# Task11.net
KiCad netlist of a schematic drawn in EAGLE
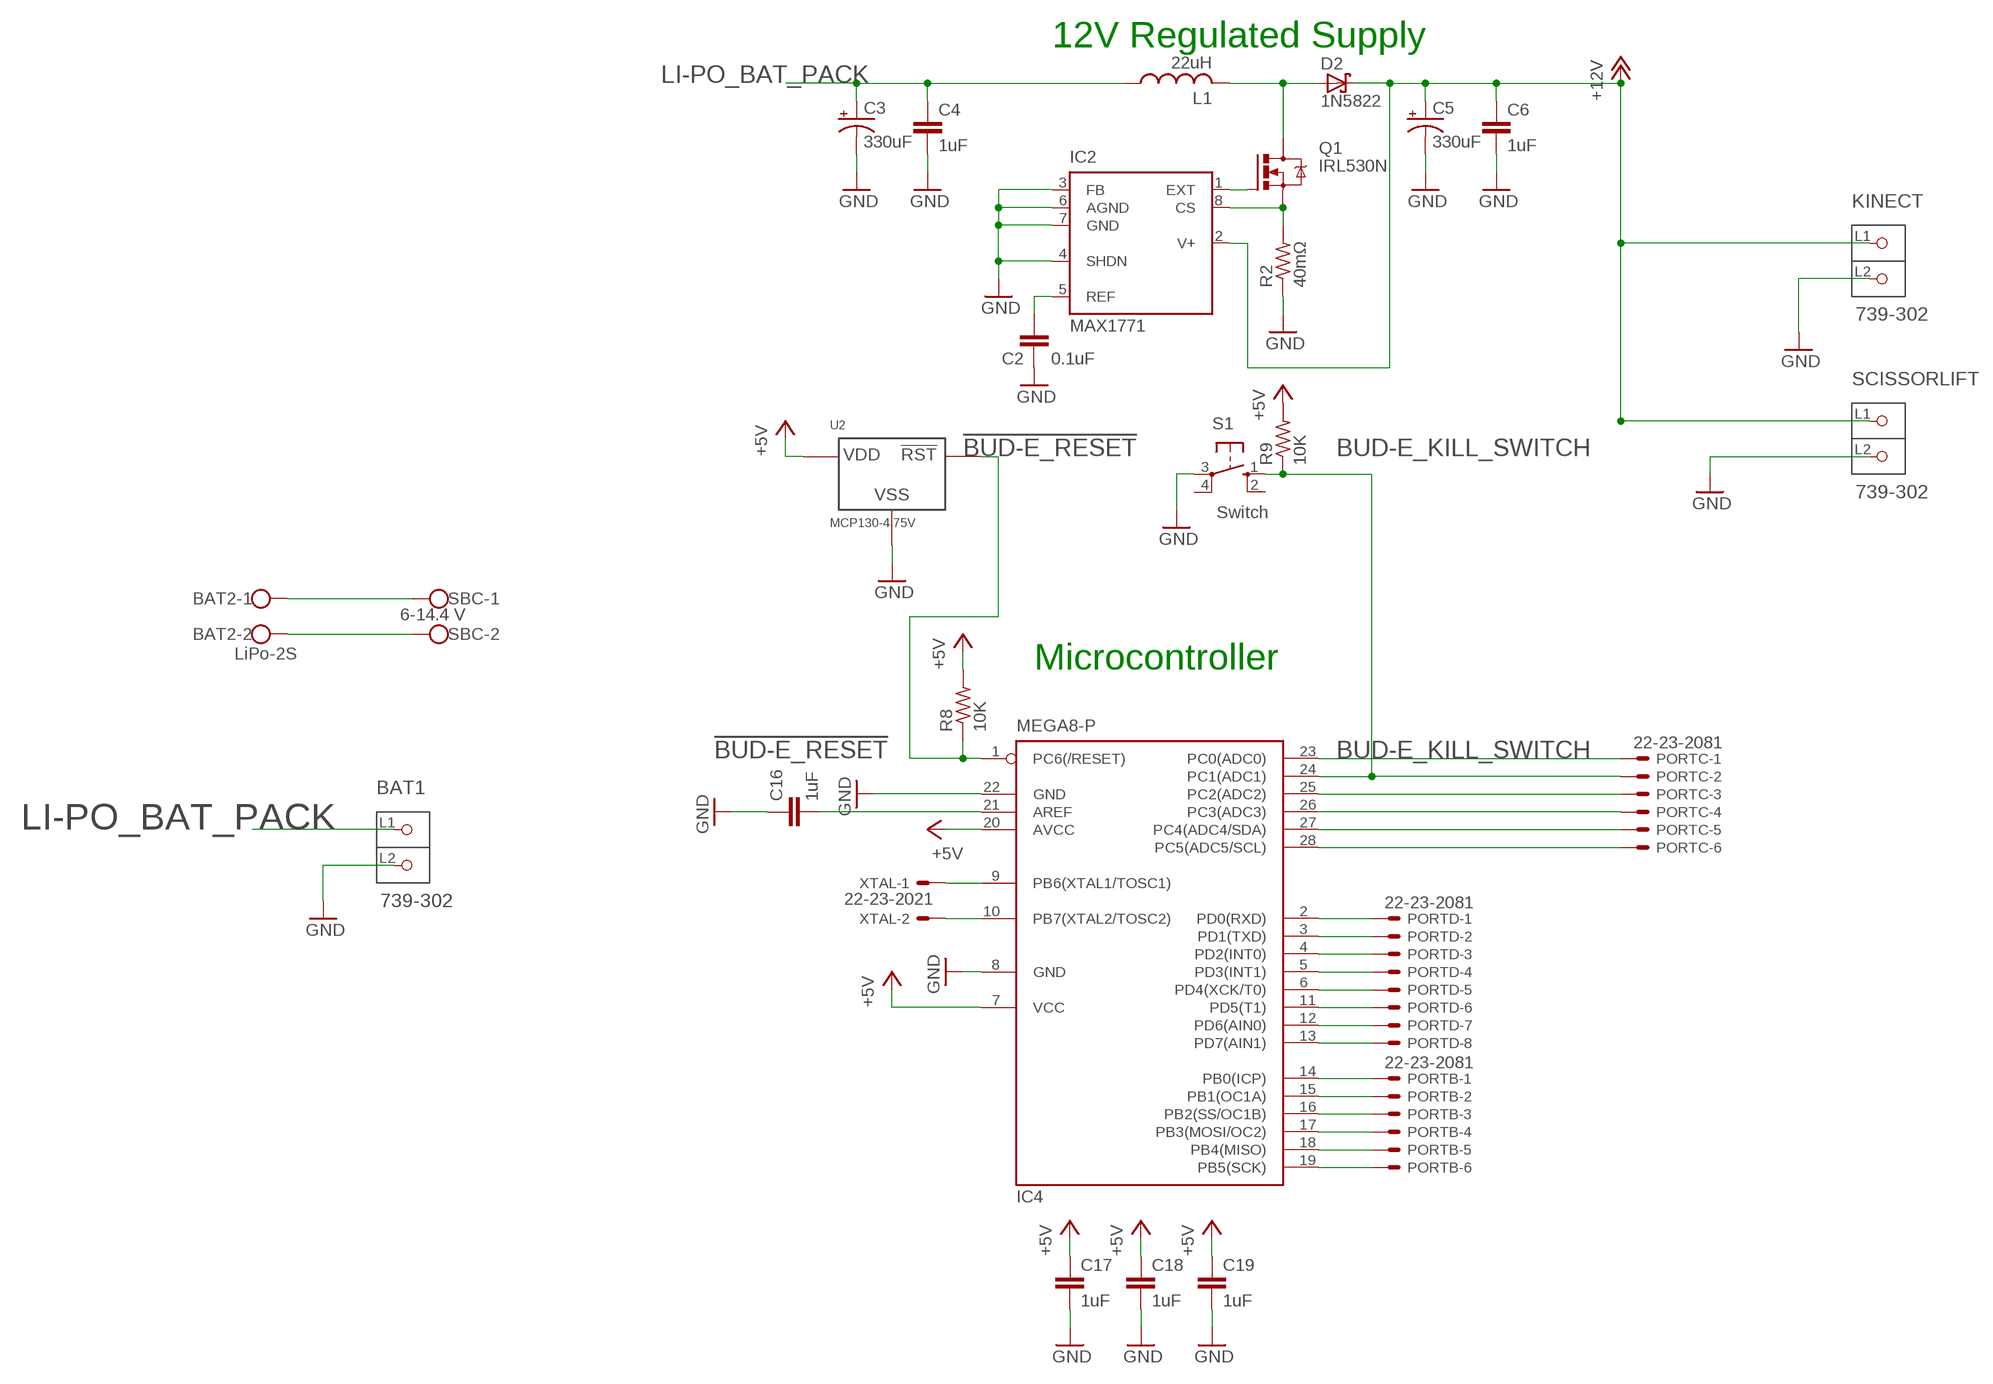
[diagram p0: schematic, sheet 1]

(export (version "E")
  (design (tool "Eeschema 10.0.6"))
  (components
    (comp (ref "BAT1")
      (value "739-302")
      (footprint "eagle-import:P-739-302")
      (libsource (lib "eagle-import") (part "739-302"))
    )
    (comp (ref "BAT2")
      (value "LiPo-2S")
      (footprint "eagle-import:W237-113")
      (libsource (lib "eagle-import") (part "W237-113"))
    )
    (comp (ref "C2")
      (value "0.1uF")
      (footprint "eagle-import:C025-025X050")
      (libsource (lib "eagle-import") (part "C-EU025-025X050"))
    )
    (comp (ref "C3")
      (value "330uF")
      (footprint "eagle-import:E2,5-6")
      (libsource (lib "eagle-import") (part "CPOL-USE2.5-6"))
    )
    (comp (ref "C4")
      (value "1uF")
      (footprint "eagle-import:C025-025X050")
      (libsource (lib "eagle-import") (part "C-EU025-025X050"))
    )
    (comp (ref "C5")
      (value "330uF")
      (footprint "eagle-import:E2,5-6")
      (libsource (lib "eagle-import") (part "CPOL-USE2.5-6"))
    )
    (comp (ref "C6")
      (value "1uF")
      (footprint "eagle-import:C025-025X050")
      (libsource (lib "eagle-import") (part "C-EU025-025X050"))
    )
    (comp (ref "C16")
      (value "1uF")
      (footprint "eagle-import:C025-025X050")
      (libsource (lib "eagle-import") (part "C-EU025-025X050"))
    )
    (comp (ref "C17")
      (value "1uF")
      (footprint "eagle-import:C025-025X050")
      (libsource (lib "eagle-import") (part "C-EU025-025X050"))
    )
    (comp (ref "C18")
      (value "1uF")
      (footprint "eagle-import:C025-025X050")
      (libsource (lib "eagle-import") (part "C-EU025-025X050"))
    )
    (comp (ref "C19")
      (value "1uF")
      (footprint "eagle-import:C025-025X050")
      (libsource (lib "eagle-import") (part "C-EU025-025X050"))
    )
    (comp (ref "D2")
      (value "1N5822")
      (footprint "eagle-import:C4111-15")
      (libsource (lib "eagle-import") (part "1N5908"))
    )
    (comp (ref "IC2")
      (value "MAX1771")
      (footprint "eagle-import:DIL08")
      (libsource (lib "eagle-import") (part "MAX1771"))
    )
    (comp (ref "IC4")
      (value "MEGA8-P")
      (footprint "eagle-import:DIL28-3")
      (libsource (lib "eagle-import") (part "MEGA8-P"))
    )
    (comp (ref "KINECT")
      (value "739-302")
      (footprint "eagle-import:P-739-302")
      (libsource (lib "eagle-import") (part "739-302"))
    )
    (comp (ref "L1")
      (value "22uH")
      (footprint "eagle-import:0207_15")
      (libsource (lib "eagle-import") (part "L-US0207/15"))
    )
    (comp (ref "PORTB")
      (value "22-23-2081")
      (footprint "eagle-import:22-23-2061")
      (fields (field (name "MF") "MOLEX") (field (name "MPN") "22-23-2061"))
      (libsource (lib "eagle-import") (part "22-23-2061"))
    )
    (comp (ref "PORTC")
      (value "22-23-2081")
      (footprint "eagle-import:22-23-2061")
      (fields (field (name "MF") "MOLEX") (field (name "MPN") "22-23-2061"))
      (libsource (lib "eagle-import") (part "22-23-2061"))
    )
    (comp (ref "PORTD")
      (value "22-23-2081")
      (footprint "eagle-import:22-23-2081")
      (fields (field (name "MF") "MOLEX"))
      (libsource (lib "eagle-import") (part "22-23-2081"))
    )
    (comp (ref "Q1")
      (value "IRL530N")
      (footprint "eagle-import:TO220BV")
      (libsource (lib "eagle-import") (part "IRF530"))
    )
    (comp (ref "R2")
      (value "40mΩ")
      (footprint "eagle-import:0207_12")
      (libsource (lib "eagle-import") (part "R-US_0207/12"))
    )
    (comp (ref "R8")
      (value "10K")
      (footprint "eagle-import:0204_7")
      (libsource (lib "eagle-import") (part "R-US_0204/7"))
    )
    (comp (ref "R9")
      (value "10K")
      (footprint "eagle-import:0204_7")
      (libsource (lib "eagle-import") (part "R-US_0204/7"))
    )
    (comp (ref "S1")
      (value "Switch")
      (footprint "eagle-import:B3F-10XX")
      (fields (field (name "MPN") "B3F-1000"))
      (libsource (lib "eagle-import") (part "10-XX"))
    )
    (comp (ref "SBC")
      (value "6-14.4 V")
      (footprint "eagle-import:W237-113")
      (libsource (lib "eagle-import") (part "W237-113"))
    )
    (comp (ref "SCISSORLIFT")
      (value "739-302")
      (footprint "eagle-import:P-739-302")
      (libsource (lib "eagle-import") (part "739-302"))
    )
    (comp (ref "U2")
      (value "MCP130-4.75V")
      (footprint "eagle-import:TO92")
      (libsource (lib "eagle-import") (part "MCP130'"))
    )
    (comp (ref "XTAL")
      (value "22-23-2021")
      (footprint "eagle-import:22-23-2021")
      (fields (field (name "MF") "MOLEX"))
      (libsource (lib "eagle-import") (part "22-23-2021"))
    )
  )
  (nets
    (net (code "1") (name "+5V") (class "Default")
      (node (ref "C17") (pin "1") (pinfunction "1_1") (pintype "passive"))
      (node (ref "C18") (pin "1") (pinfunction "1_1") (pintype "passive"))
      (node (ref "C19") (pin "1") (pinfunction "1_1") (pintype "passive"))
      (node (ref "IC4") (pin "20") (pinfunction "AVCC_20") (pintype "power_in"))
      (node (ref "IC4") (pin "7") (pinfunction "VCC_7") (pintype "power_in"))
      (node (ref "R8") (pin "2") (pinfunction "2_2") (pintype "passive"))
      (node (ref "R9") (pin "2") (pinfunction "2_2") (pintype "passive"))
      (node (ref "U2") (pin "2") (pinfunction "VDD_2") (pintype "bidirectional"))
    )
    (net (code "2") (name "+12V") (class "Default")
      (node (ref "C5") (pin "+") (pinfunction "+_+") (pintype "passive"))
      (node (ref "C6") (pin "1") (pinfunction "1_1") (pintype "passive"))
      (node (ref "D2") (pin "C") (pinfunction "C_C") (pintype "passive"))
      (node (ref "IC2") (pin "2") (pinfunction "V+_2") (pintype "input"))
      (node (ref "KINECT") (pin "L1") (pinfunction "P1_L1") (pintype "bidirectional"))
      (node (ref "SCISSORLIFT") (pin "L1") (pinfunction "P1_L1") (pintype "bidirectional"))
    )
    (net (code "3") (name "/BUD-E_KILL_SWITCH") (class "Default")
      (node (ref "IC4") (pin "24") (pinfunction "PC1(ADC1)_24") (pintype "bidirectional"))
      (node (ref "PORTC") (pin "2") (pinfunction "S_2") (pintype "passive"))
      (node (ref "R9") (pin "1") (pinfunction "1_1") (pintype "passive"))
      (node (ref "S1") (pin "1") (pinfunction "S_1") (pintype "passive"))
    )
    (net (code "4") (name "/LI-PO_BAT_PACK") (class "Default")
      (node (ref "BAT1") (pin "L1") (pinfunction "P1_L1") (pintype "bidirectional"))
      (node (ref "C3") (pin "+") (pinfunction "+_+") (pintype "passive"))
      (node (ref "C4") (pin "1") (pinfunction "1_1") (pintype "passive"))
      (node (ref "L1") (pin "1") (pinfunction "1_1") (pintype "passive"))
    )
    (net (code "5") (name "/~{BUD-E_RESET}") (class "Default")
      (node (ref "IC4") (pin "1") (pinfunction "PC6(/RESET)_1") (pintype "bidirectional"))
      (node (ref "R8") (pin "1") (pinfunction "1_1") (pintype "passive"))
      (node (ref "U2") (pin "1") (pinfunction "~{RST}_1") (pintype "bidirectional"))
    )
    (net (code "6") (name "GND") (class "Default")
      (node (ref "BAT1") (pin "L2") (pinfunction "P2_L2") (pintype "bidirectional"))
      (node (ref "C16") (pin "1") (pinfunction "1_1") (pintype "passive"))
      (node (ref "C17") (pin "2") (pinfunction "2_2") (pintype "passive"))
      (node (ref "C18") (pin "2") (pinfunction "2_2") (pintype "passive"))
      (node (ref "C19") (pin "2") (pinfunction "2_2") (pintype "passive"))
      (node (ref "C2") (pin "1") (pinfunction "1_1") (pintype "passive"))
      (node (ref "C3") (pin "-") (pinfunction "-_-") (pintype "passive"))
      (node (ref "C4") (pin "2") (pinfunction "2_2") (pintype "passive"))
      (node (ref "C5") (pin "-") (pinfunction "-_-") (pintype "passive"))
      (node (ref "C6") (pin "2") (pinfunction "2_2") (pintype "passive"))
      (node (ref "IC2") (pin "3") (pinfunction "FB_3") (pintype "input"))
      (node (ref "IC2") (pin "4") (pinfunction "SHDN_4") (pintype "input"))
      (node (ref "IC2") (pin "6") (pinfunction "AGND_6") (pintype "power_in"))
      (node (ref "IC2") (pin "7") (pinfunction "GND_7") (pintype "power_in"))
      (node (ref "IC4") (pin "22") (pinfunction "GND_22") (pintype "power_in"))
      (node (ref "IC4") (pin "8") (pinfunction "GND_8") (pintype "power_in"))
      (node (ref "KINECT") (pin "L2") (pinfunction "P2_L2") (pintype "bidirectional"))
      (node (ref "R2") (pin "1") (pinfunction "1_1") (pintype "passive"))
      (node (ref "S1") (pin "3") (pinfunction "P_3") (pintype "passive"))
      (node (ref "SCISSORLIFT") (pin "L2") (pinfunction "P2_L2") (pintype "bidirectional"))
      (node (ref "U2") (pin "3") (pinfunction "VSS_3") (pintype "bidirectional"))
    )
    (net (code "7") (name "Net-(BAT2A-KL)") (class "Default")
      (node (ref "BAT2") (pin "1") (pinfunction "KL_1") (pintype "passive"))
      (node (ref "SBC") (pin "1") (pinfunction "KL_1") (pintype "passive"))
    )
    (net (code "8") (name "Net-(BAT2B-KL)") (class "Default")
      (node (ref "BAT2") (pin "2") (pinfunction "KL_2") (pintype "passive"))
      (node (ref "SBC") (pin "2") (pinfunction "KL_2") (pintype "passive"))
    )
    (net (code "9") (name "Net-(D2-PadA)") (class "Default")
      (node (ref "D2") (pin "A") (pinfunction "A_A") (pintype "passive"))
      (node (ref "L1") (pin "2") (pinfunction "2_2") (pintype "passive"))
      (node (ref "Q1") (pin "D") (pinfunction "D_D") (pintype "passive"))
    )
    (net (code "10") (name "Net-(IC2-CS)") (class "Default")
      (node (ref "IC2") (pin "8") (pinfunction "CS_8") (pintype "input"))
      (node (ref "Q1") (pin "S") (pinfunction "S_S") (pintype "passive"))
      (node (ref "R2") (pin "2") (pinfunction "2_2") (pintype "passive"))
    )
    (net (code "11") (name "Net-(IC2-EXT)") (class "Default")
      (node (ref "IC2") (pin "1") (pinfunction "EXT_1") (pintype "output"))
      (node (ref "Q1") (pin "G") (pinfunction "G_G") (pintype "passive"))
    )
    (net (code "12") (name "Net-(IC2-REF)") (class "Default")
      (node (ref "C2") (pin "2") (pinfunction "2_2") (pintype "passive"))
      (node (ref "IC2") (pin "5") (pinfunction "REF_5") (pintype "input"))
    )
    (net (code "13") (name "Net-(IC4-AREF)") (class "Default")
      (node (ref "C16") (pin "2") (pinfunction "2_2") (pintype "passive"))
      (node (ref "IC4") (pin "21") (pinfunction "AREF_21") (pintype "passive"))
    )
    (net (code "14") (name "Net-(IC4-PB0(ICP))") (class "Default")
      (node (ref "IC4") (pin "14") (pinfunction "PB0(ICP)_14") (pintype "bidirectional"))
      (node (ref "PORTB") (pin "1") (pinfunction "S_1") (pintype "passive"))
    )
    (net (code "15") (name "Net-(IC4-PB1(OC1A))") (class "Default")
      (node (ref "IC4") (pin "15") (pinfunction "PB1(OC1A)_15") (pintype "bidirectional"))
      (node (ref "PORTB") (pin "2") (pinfunction "S_2") (pintype "passive"))
    )
    (net (code "16") (name "Net-(IC4-PB2(SS{slash}OC1B))") (class "Default")
      (node (ref "IC4") (pin "16") (pinfunction "PB2(SS/OC1B)_16") (pintype "bidirectional"))
      (node (ref "PORTB") (pin "3") (pinfunction "S_3") (pintype "passive"))
    )
    (net (code "17") (name "Net-(IC4-PB3(MOSI{slash}OC2))") (class "Default")
      (node (ref "IC4") (pin "17") (pinfunction "PB3(MOSI/OC2)_17") (pintype "bidirectional"))
      (node (ref "PORTB") (pin "4") (pinfunction "S_4") (pintype "passive"))
    )
    (net (code "18") (name "Net-(IC4-PB4(MISO))") (class "Default")
      (node (ref "IC4") (pin "18") (pinfunction "PB4(MISO)_18") (pintype "bidirectional"))
      (node (ref "PORTB") (pin "5") (pinfunction "S_5") (pintype "passive"))
    )
    (net (code "19") (name "Net-(IC4-PB5(SCK))") (class "Default")
      (node (ref "IC4") (pin "19") (pinfunction "PB5(SCK)_19") (pintype "bidirectional"))
      (node (ref "PORTB") (pin "6") (pinfunction "S_6") (pintype "passive"))
    )
    (net (code "20") (name "Net-(IC4-PB6(XTAL1{slash}TOSC1))") (class "Default")
      (node (ref "IC4") (pin "9") (pinfunction "PB6(XTAL1/TOSC1)_9") (pintype "bidirectional"))
      (node (ref "XTAL") (pin "1") (pinfunction "S_1") (pintype "passive"))
    )
    (net (code "21") (name "Net-(IC4-PB7(XTAL2{slash}TOSC2))") (class "Default")
      (node (ref "IC4") (pin "10") (pinfunction "PB7(XTAL2/TOSC2)_10") (pintype "bidirectional"))
      (node (ref "XTAL") (pin "2") (pinfunction "S_2") (pintype "passive"))
    )
    (net (code "22") (name "Net-(IC4-PC0(ADC0))") (class "Default")
      (node (ref "IC4") (pin "23") (pinfunction "PC0(ADC0)_23") (pintype "bidirectional"))
      (node (ref "PORTC") (pin "1") (pinfunction "S_1") (pintype "passive"))
    )
    (net (code "23") (name "Net-(IC4-PC2(ADC2))") (class "Default")
      (node (ref "IC4") (pin "25") (pinfunction "PC2(ADC2)_25") (pintype "bidirectional"))
      (node (ref "PORTC") (pin "3") (pinfunction "S_3") (pintype "passive"))
    )
    (net (code "24") (name "Net-(IC4-PC3(ADC3))") (class "Default")
      (node (ref "IC4") (pin "26") (pinfunction "PC3(ADC3)_26") (pintype "bidirectional"))
      (node (ref "PORTC") (pin "4") (pinfunction "S_4") (pintype "passive"))
    )
    (net (code "25") (name "Net-(IC4-PC4(ADC4{slash}SDA))") (class "Default")
      (node (ref "IC4") (pin "27") (pinfunction "PC4(ADC4/SDA)_27") (pintype "bidirectional"))
      (node (ref "PORTC") (pin "5") (pinfunction "S_5") (pintype "passive"))
    )
    (net (code "26") (name "Net-(IC4-PC5(ADC5{slash}SCL))") (class "Default")
      (node (ref "IC4") (pin "28") (pinfunction "PC5(ADC5/SCL)_28") (pintype "bidirectional"))
      (node (ref "PORTC") (pin "6") (pinfunction "S_6") (pintype "passive"))
    )
    (net (code "27") (name "Net-(IC4-PD0(RXD))") (class "Default")
      (node (ref "IC4") (pin "2") (pinfunction "PD0(RXD)_2") (pintype "bidirectional"))
      (node (ref "PORTD") (pin "1") (pinfunction "S_1") (pintype "passive"))
    )
    (net (code "28") (name "Net-(IC4-PD1(TXD))") (class "Default")
      (node (ref "IC4") (pin "3") (pinfunction "PD1(TXD)_3") (pintype "bidirectional"))
      (node (ref "PORTD") (pin "2") (pinfunction "S_2") (pintype "passive"))
    )
    (net (code "29") (name "Net-(IC4-PD2(INT0))") (class "Default")
      (node (ref "IC4") (pin "4") (pinfunction "PD2(INT0)_4") (pintype "bidirectional"))
      (node (ref "PORTD") (pin "3") (pinfunction "S_3") (pintype "passive"))
    )
    (net (code "30") (name "Net-(IC4-PD3(INT1))") (class "Default")
      (node (ref "IC4") (pin "5") (pinfunction "PD3(INT1)_5") (pintype "bidirectional"))
      (node (ref "PORTD") (pin "4") (pinfunction "S_4") (pintype "passive"))
    )
    (net (code "31") (name "Net-(IC4-PD4(XCK{slash}T0))") (class "Default")
      (node (ref "IC4") (pin "6") (pinfunction "PD4(XCK/T0)_6") (pintype "bidirectional"))
      (node (ref "PORTD") (pin "5") (pinfunction "S_5") (pintype "passive"))
    )
    (net (code "32") (name "Net-(IC4-PD5(T1))") (class "Default")
      (node (ref "IC4") (pin "11") (pinfunction "PD5(T1)_11") (pintype "bidirectional"))
      (node (ref "PORTD") (pin "6") (pinfunction "S_6") (pintype "passive"))
    )
    (net (code "33") (name "Net-(IC4-PD6(AIN0))") (class "Default")
      (node (ref "IC4") (pin "12") (pinfunction "PD6(AIN0)_12") (pintype "bidirectional"))
      (node (ref "PORTD") (pin "7") (pinfunction "S_7") (pintype "passive"))
    )
    (net (code "34") (name "Net-(IC4-PD7(AIN1))") (class "Default")
      (node (ref "IC4") (pin "13") (pinfunction "PD7(AIN1)_13") (pintype "bidirectional"))
      (node (ref "PORTD") (pin "8") (pinfunction "S_8") (pintype "passive"))
    )
    (net (code "35") (name "unconnected-(S1-P1-Pad4)") (class "Default")
      (node (ref "S1") (pin "4") (pinfunction "P1_4") (pintype "passive"))
    )
    (net (code "36") (name "unconnected-(S1-S1-Pad2)") (class "Default")
      (node (ref "S1") (pin "2") (pinfunction "S1_2") (pintype "passive"))
    )
  )
)
